# Me-Servo_Driver_v2_1.net
KiCad netlist of a schematic drawn in EAGLE
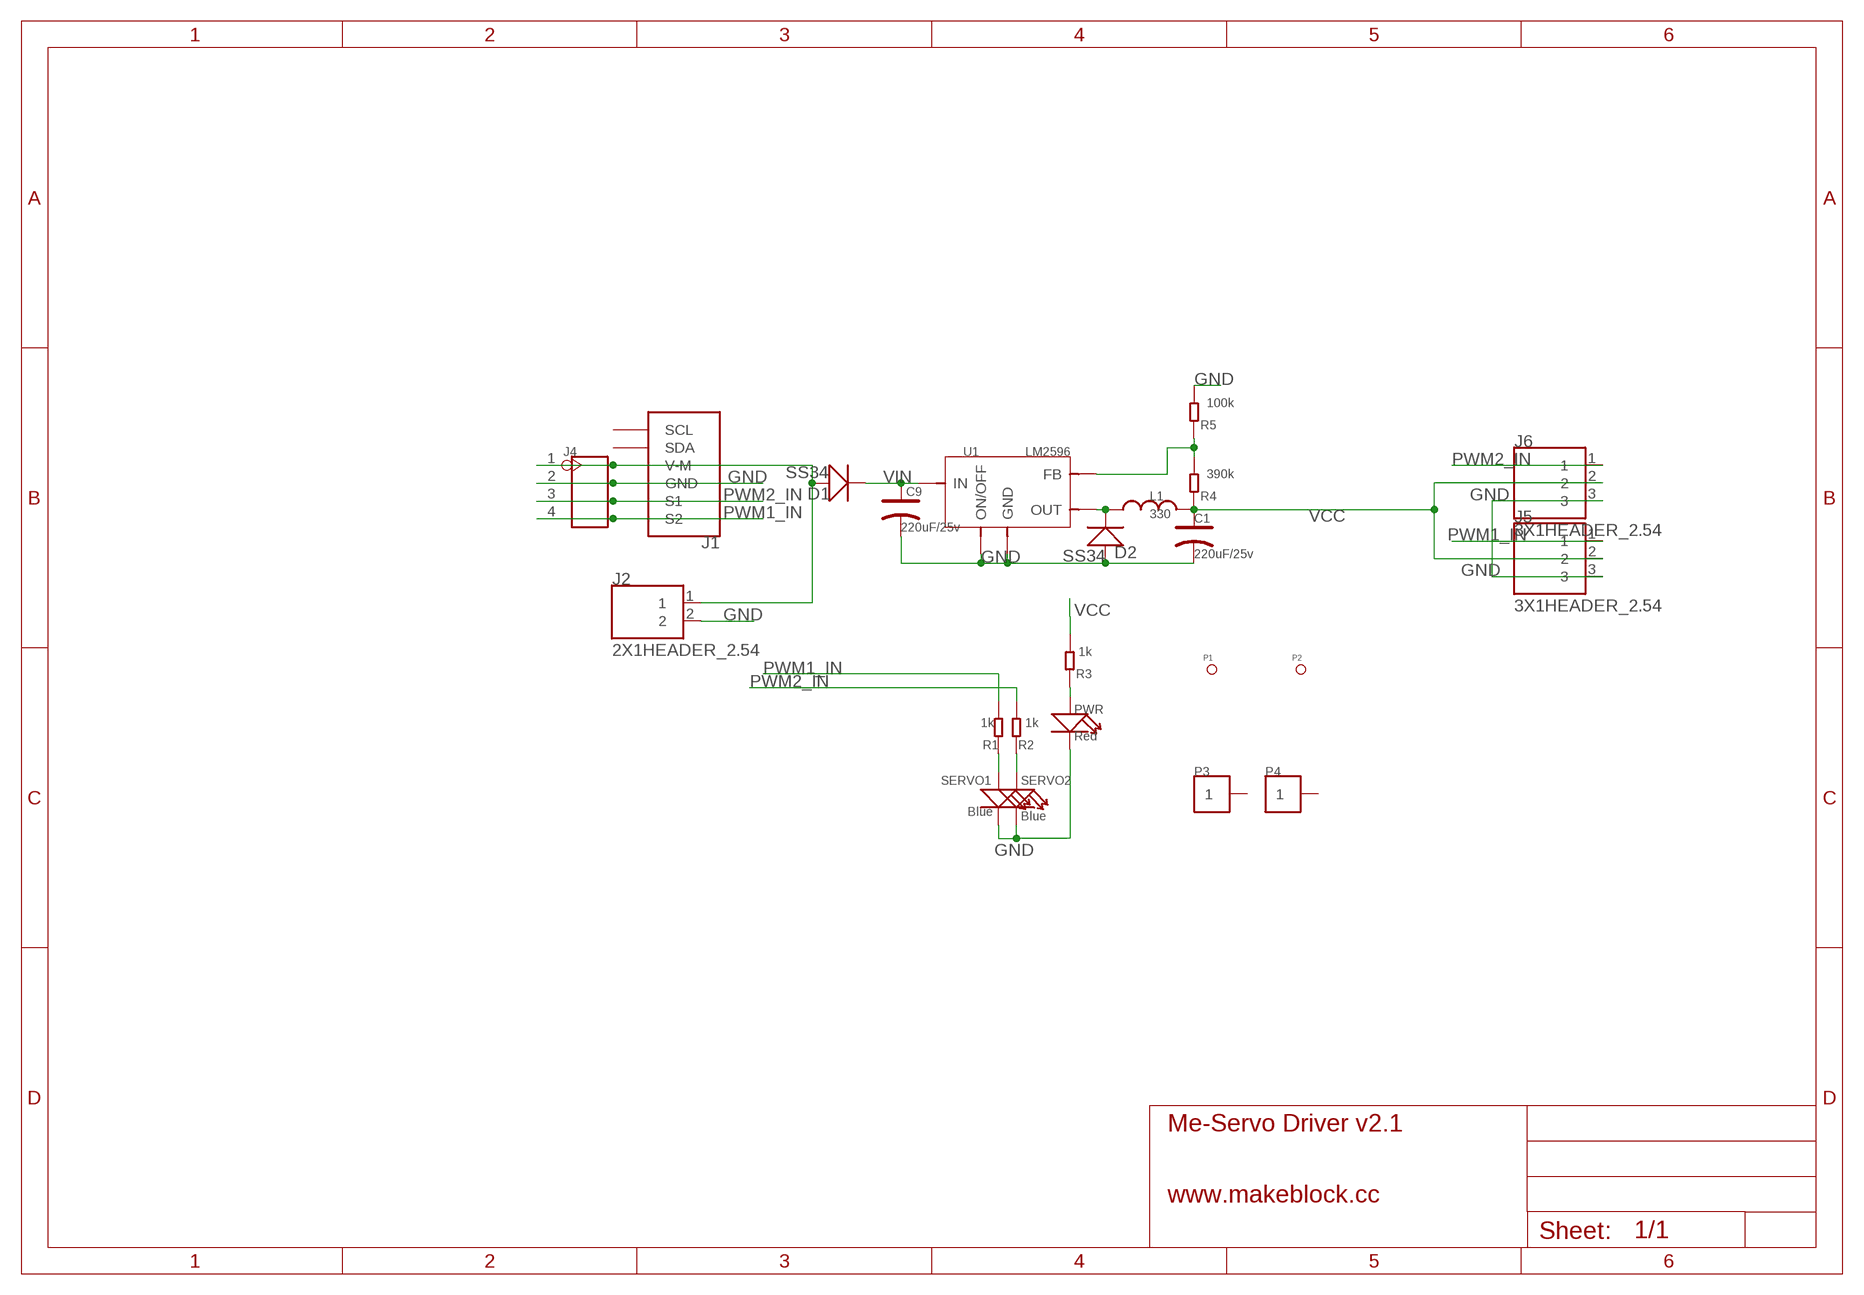
[diagram p0: schematic, sheet 1]

(export (version "E")
  (design (tool "Eeschema 10.0.6"))
  (components
    (comp (ref "C1")
      (value "220uF/25v")
      (footprint "eagle-import:ELECTRO-SMD-E-7.8MM")
      (libsource (lib "eagle-import") (part "CAP-ELECTRO-E"))
    )
    (comp (ref "C9")
      (value "220uF/25v")
      (footprint "eagle-import:ELECTRO-SMD-E-7.8MM")
      (libsource (lib "eagle-import") (part "CAP-ELECTRO-E"))
    )
    (comp (ref "D1")
      (value "SS34")
      (footprint "eagle-import:D2010")
      (libsource (lib "eagle-import") (part "D'SMA'"))
    )
    (comp (ref "D2")
      (value "SS34")
      (footprint "eagle-import:D2010")
      (libsource (lib "eagle-import") (part "D'SMA'"))
    )
    (comp (ref "J1")
      (value "RJ11-6P6C-MOTOR")
      (footprint "eagle-import:RJ11-6P6C")
      (libsource (lib "eagle-import") (part "RJ11-6P6C-MOTOR"))
    )
    (comp (ref "J2")
      (value "2X1HEADER_2.54")
      (footprint "eagle-import:2X1HEADER_2.54")
      (libsource (lib "eagle-import") (part "2X1HEADER_2.54"))
    )
    (comp (ref "J4")
      (value "HEADER-4P-60/35MIL")
      (footprint "eagle-import:4P-65_35MIL")
      (libsource (lib "eagle-import") (part "HEADER-4P-60/35MIL"))
    )
    (comp (ref "J5")
      (value "3X1HEADER_2.54")
      (footprint "eagle-import:3X1HEADER_2.54")
      (libsource (lib "eagle-import") (part "3X1HEADER_2.54"))
    )
    (comp (ref "J6")
      (value "3X1HEADER_2.54")
      (footprint "eagle-import:3X1HEADER_2.54")
      (libsource (lib "eagle-import") (part "3X1HEADER_2.54"))
    )
    (comp (ref "L1")
      (value "330")
      (footprint "eagle-import:12X12_INDUCTANCE")
      (libsource (lib "eagle-import") (part "12X12_INDUCTANCE"))
    )
    (comp (ref "P1")
      (value "PAD-MARK")
      (footprint "eagle-import:ROUND-MARK-1.0")
      (fields (field (name "PARTNO") "DNP"))
      (libsource (lib "eagle-import") (part "PAD-MARK"))
    )
    (comp (ref "P2")
      (value "PAD-MARK")
      (footprint "eagle-import:ROUND-MARK-1.0")
      (fields (field (name "PARTNO") "DNP"))
      (libsource (lib "eagle-import") (part "PAD-MARK"))
    )
    (comp (ref "P3")
      (value "PAD-1P-4MM")
      (footprint "eagle-import:HOLE-01")
      (libsource (lib "eagle-import") (part "PAD-1P-4MM"))
    )
    (comp (ref "P4")
      (value "PAD-1P-4MM")
      (footprint "eagle-import:HOLE-01")
      (libsource (lib "eagle-import") (part "PAD-1P-4MM"))
    )
    (comp (ref "PWR")
      (value "Red")
      (footprint "eagle-import:LED-0603")
      (libsource (lib "eagle-import") (part "LED'0603'"))
    )
    (comp (ref "R1")
      (value "1k")
      (footprint "eagle-import:0603")
      (libsource (lib "eagle-import") (part "R-0603"))
    )
    (comp (ref "R2")
      (value "1k")
      (footprint "eagle-import:0603")
      (libsource (lib "eagle-import") (part "R-0603"))
    )
    (comp (ref "R3")
      (value "1k")
      (footprint "eagle-import:0603")
      (libsource (lib "eagle-import") (part "R-0603"))
    )
    (comp (ref "R4")
      (value "390k")
      (footprint "eagle-import:0603")
      (libsource (lib "eagle-import") (part "R-0603"))
    )
    (comp (ref "R5")
      (value "100k")
      (footprint "eagle-import:0603")
      (libsource (lib "eagle-import") (part "R-0603"))
    )
    (comp (ref "SERVO1")
      (value "Blue")
      (footprint "eagle-import:LED-0603")
      (libsource (lib "eagle-import") (part "LED'0603'"))
    )
    (comp (ref "SERVO2")
      (value "Blue")
      (footprint "eagle-import:LED-0603")
      (libsource (lib "eagle-import") (part "LED'0603'"))
    )
    (comp (ref "U1")
      (value "LM2596")
      (footprint "eagle-import:LM2596")
      (libsource (lib "eagle-import") (part "LM2596"))
    )
  )
  (nets
    (net (code "1") (name "/GND") (class "Default")
      (node (ref "C1") (pin "-") (pinfunction "-_-") (pintype "passive"))
      (node (ref "C9") (pin "-") (pinfunction "-_-") (pintype "passive"))
      (node (ref "D2") (pin "+") (pinfunction "+_+") (pintype "passive"))
      (node (ref "J1") (pin "4") (pinfunction "GND_4") (pintype "bidirectional"))
      (node (ref "J2") (pin "2") (pinfunction "2_2") (pintype "bidirectional"))
      (node (ref "J4") (pin "2") (pinfunction "P$2_2") (pintype "bidirectional"))
      (node (ref "J5") (pin "3") (pinfunction "3_3") (pintype "bidirectional"))
      (node (ref "J6") (pin "3") (pinfunction "3_3") (pintype "bidirectional"))
      (node (ref "PWR") (pin "-") (pinfunction "-_-") (pintype "passive"))
      (node (ref "R5") (pin "2") (pinfunction "2_2") (pintype "passive"))
      (node (ref "SERVO1") (pin "-") (pinfunction "-_-") (pintype "passive"))
      (node (ref "SERVO2") (pin "-") (pinfunction "-_-") (pintype "passive"))
      (node (ref "U1") (pin "3") (pinfunction "GND_3") (pintype "bidirectional"))
      (node (ref "U1") (pin "4") (pinfunction "GND_4") (pintype "bidirectional"))
      (node (ref "U1") (pin "6") (pinfunction "ON/OFF_6") (pintype "bidirectional"))
    )
    (net (code "2") (name "/PWM1_IN") (class "Default")
      (node (ref "J1") (pin "6") (pinfunction "S2_6") (pintype "bidirectional"))
      (node (ref "J4") (pin "4") (pinfunction "P$4_4") (pintype "bidirectional"))
      (node (ref "J5") (pin "1") (pinfunction "1_1") (pintype "bidirectional"))
      (node (ref "R1") (pin "2") (pinfunction "2_2") (pintype "passive"))
    )
    (net (code "3") (name "/PWM2_IN") (class "Default")
      (node (ref "J1") (pin "5") (pinfunction "S1_5") (pintype "bidirectional"))
      (node (ref "J4") (pin "3") (pinfunction "P$3_3") (pintype "bidirectional"))
      (node (ref "J6") (pin "1") (pinfunction "1_1") (pintype "bidirectional"))
      (node (ref "R2") (pin "2") (pinfunction "2_2") (pintype "passive"))
    )
    (net (code "4") (name "/VCC") (class "Default")
      (node (ref "C1") (pin "+") (pinfunction "+_+") (pintype "passive"))
      (node (ref "J5") (pin "2") (pinfunction "2_2") (pintype "bidirectional"))
      (node (ref "J6") (pin "2") (pinfunction "2_2") (pintype "bidirectional"))
      (node (ref "L1") (pin "P$2") (pinfunction "2_P$2") (pintype "bidirectional"))
      (node (ref "R3") (pin "2") (pinfunction "2_2") (pintype "passive"))
      (node (ref "R4") (pin "1") (pinfunction "1_1") (pintype "passive"))
    )
    (net (code "5") (name "/VIN") (class "Default")
      (node (ref "C9") (pin "+") (pinfunction "+_+") (pintype "passive"))
      (node (ref "D1") (pin "-") (pinfunction "-_-") (pintype "passive"))
      (node (ref "U1") (pin "1") (pinfunction "IN_1") (pintype "bidirectional"))
    )
    (net (code "6") (name "Net-(J1-V-M)") (class "Default")
      (node (ref "D1") (pin "+") (pinfunction "+_+") (pintype "passive"))
      (node (ref "J1") (pin "3") (pinfunction "V-M_3") (pintype "bidirectional"))
      (node (ref "J2") (pin "1") (pinfunction "1_1") (pintype "bidirectional"))
      (node (ref "J4") (pin "1") (pinfunction "P$1_1") (pintype "bidirectional"))
    )
    (net (code "7") (name "Net-(L1-1)") (class "Default")
      (node (ref "D2") (pin "-") (pinfunction "-_-") (pintype "passive"))
      (node (ref "L1") (pin "P$1") (pinfunction "1_P$1") (pintype "bidirectional"))
      (node (ref "U1") (pin "2") (pinfunction "OUT_2") (pintype "bidirectional"))
    )
    (net (code "8") (name "Net-(PWR-Pad+)") (class "Default")
      (node (ref "PWR") (pin "+") (pinfunction "+_+") (pintype "passive"))
      (node (ref "R3") (pin "1") (pinfunction "1_1") (pintype "passive"))
    )
    (net (code "9") (name "Net-(R1-Pad1)") (class "Default")
      (node (ref "R1") (pin "1") (pinfunction "1_1") (pintype "passive"))
      (node (ref "SERVO1") (pin "+") (pinfunction "+_+") (pintype "passive"))
    )
    (net (code "10") (name "Net-(R2-Pad1)") (class "Default")
      (node (ref "R2") (pin "1") (pinfunction "1_1") (pintype "passive"))
      (node (ref "SERVO2") (pin "+") (pinfunction "+_+") (pintype "passive"))
    )
    (net (code "11") (name "Net-(U1-FB)") (class "Default")
      (node (ref "R4") (pin "2") (pinfunction "2_2") (pintype "passive"))
      (node (ref "R5") (pin "1") (pinfunction "1_1") (pintype "passive"))
      (node (ref "U1") (pin "5") (pinfunction "FB_5") (pintype "bidirectional"))
    )
    (net (code "12") (name "unconnected-(J1-SCL-Pad1)") (class "Default")
      (node (ref "J1") (pin "1") (pinfunction "SCL_1") (pintype "bidirectional"))
    )
    (net (code "13") (name "unconnected-(J1-SDA-Pad2)") (class "Default")
      (node (ref "J1") (pin "2") (pinfunction "SDA_2") (pintype "bidirectional"))
    )
    (net (code "14") (name "unconnected-(P3-Pad1)") (class "Default")
      (node (ref "P3") (pin "1") (pinfunction "1_1") (pintype "bidirectional"))
    )
    (net (code "15") (name "unconnected-(P4-Pad1)") (class "Default")
      (node (ref "P4") (pin "1") (pinfunction "1_1") (pintype "bidirectional"))
    )
  )
)
